# fancontrol_attiny.net
KiCad netlist of a schematic drawn in EAGLE
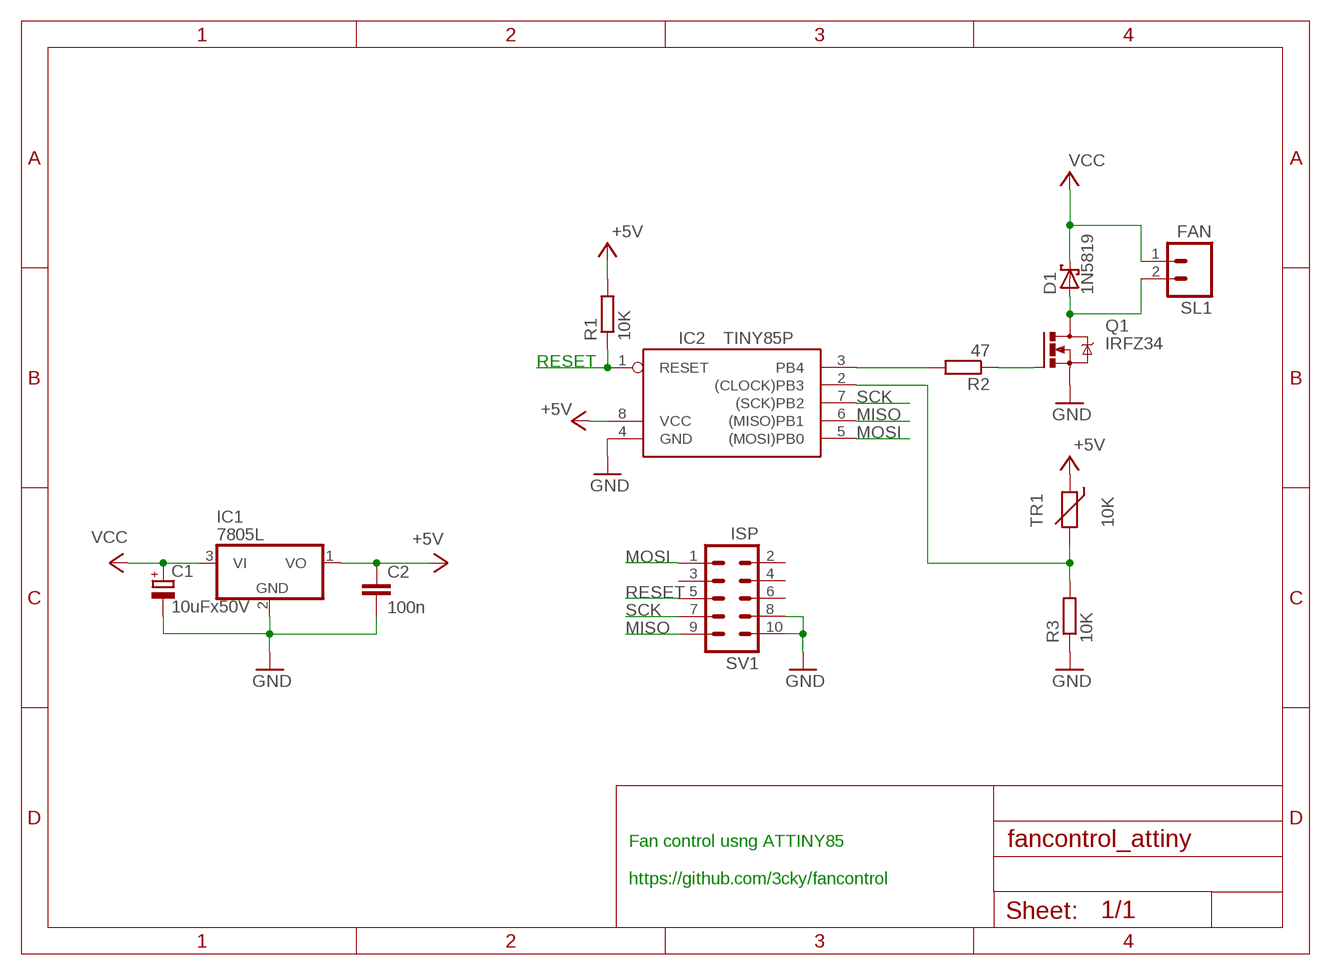
[diagram p0: schematic, sheet 1]

(export (version "E")
  (design (tool "Eeschema 10.0.6"))
  (components
    (comp (ref "C1")
      (value "10uFx50V")
      (footprint "eagle-import:E5-5")
      (libsource (lib "eagle-import") (part "CPOL-EUE5-5"))
    )
    (comp (ref "C2")
      (value "100n")
      (footprint "eagle-import:C025-024X044")
      (libsource (lib "eagle-import") (part "C-EU025-024X044"))
    )
    (comp (ref "D1")
      (value "1N5819")
      (footprint "eagle-import:DO41-7.6")
      (libsource (lib "eagle-import") (part "1N5819-B"))
    )
    (comp (ref "IC1")
      (value "7805L")
      (footprint "eagle-import:TO92")
      (libsource (lib "eagle-import") (part "78L05"))
    )
    (comp (ref "IC2")
      (value "TINY85P")
      (footprint "eagle-import:DIL08")
      (libsource (lib "eagle-import") (part "TINY22P"))
    )
    (comp (ref "Q1")
      (value "IRFZ34")
      (footprint "eagle-import:TO220BH")
      (libsource (lib "eagle-import") (part "IRFZ48Z"))
    )
    (comp (ref "R1")
      (value "10K")
      (footprint "eagle-import:M0805")
      (libsource (lib "eagle-import") (part "R-EU_M0805"))
    )
    (comp (ref "R2")
      (value "47")
      (footprint "eagle-import:M0805")
      (libsource (lib "eagle-import") (part "R-EU_M0805"))
    )
    (comp (ref "R3")
      (value "10K")
      (footprint "eagle-import:M0805")
      (libsource (lib "eagle-import") (part "R-EU_M0805"))
    )
    (comp (ref "SL1")
      (value "FAN")
      (footprint "eagle-import:02P")
      (libsource (lib "eagle-import") (part "M02"))
    )
    (comp (ref "SV1")
      (value "ISP")
      (footprint "eagle-import:MA05-2")
      (libsource (lib "eagle-import") (part "MA05-2"))
    )
    (comp (ref "TR1")
      (value "10K")
      (footprint "eagle-import:R-5")
      (libsource (lib "eagle-import") (part "THERMISTOR_R-5"))
    )
  )
  (nets
    (net (code "1") (name "+5V") (class "Default")
      (node (ref "C2") (pin "1") (pinfunction "1_1") (pintype "passive"))
      (node (ref "IC1") (pin "1") (pinfunction "VO_1") (pintype "passive"))
      (node (ref "IC2") (pin "8") (pinfunction "VCC_8") (pintype "power_in"))
      (node (ref "R1") (pin "2") (pinfunction "2_2") (pintype "passive"))
      (node (ref "TR1") (pin "1") (pinfunction "1_1") (pintype "passive"))
    )
    (net (code "2") (name "/MISO") (class "Default")
      (node (ref "IC2") (pin "6") (pinfunction "(MISO)PB1_6") (pintype "bidirectional"))
      (node (ref "SV1") (pin "9") (pinfunction "9_9") (pintype "passive"))
    )
    (net (code "3") (name "/MOSI") (class "Default")
      (node (ref "IC2") (pin "5") (pinfunction "(MOSI)PB0_5") (pintype "bidirectional"))
      (node (ref "SV1") (pin "1") (pinfunction "1_1") (pintype "passive"))
    )
    (net (code "4") (name "/RESET") (class "Default")
      (node (ref "IC2") (pin "1") (pinfunction "RESET_1") (pintype "input"))
      (node (ref "R1") (pin "1") (pinfunction "1_1") (pintype "passive"))
      (node (ref "SV1") (pin "5") (pinfunction "5_5") (pintype "passive"))
    )
    (net (code "5") (name "/SCK") (class "Default")
      (node (ref "IC2") (pin "7") (pinfunction "(SCK)PB2_7") (pintype "bidirectional"))
      (node (ref "SV1") (pin "7") (pinfunction "7_7") (pintype "passive"))
    )
    (net (code "6") (name "GND") (class "Default")
      (node (ref "C1") (pin "-") (pinfunction "-_-") (pintype "passive"))
      (node (ref "C2") (pin "2") (pinfunction "2_2") (pintype "passive"))
      (node (ref "IC1") (pin "2") (pinfunction "GND_2") (pintype "passive"))
      (node (ref "IC2") (pin "4") (pinfunction "GND_4") (pintype "power_in"))
      (node (ref "Q1") (pin "S") (pinfunction "S_S") (pintype "passive"))
      (node (ref "R3") (pin "1") (pinfunction "1_1") (pintype "passive"))
      (node (ref "SV1") (pin "10") (pinfunction "10_10") (pintype "passive"))
      (node (ref "SV1") (pin "8") (pinfunction "8_8") (pintype "passive"))
    )
    (net (code "7") (name "Net-(D1-PadA)") (class "Default")
      (node (ref "D1") (pin "A") (pinfunction "A_A") (pintype "passive"))
      (node (ref "Q1") (pin "D") (pinfunction "D_D") (pintype "passive"))
      (node (ref "SL1") (pin "2") (pinfunction "2_2") (pintype "passive"))
    )
    (net (code "8") (name "Net-(IC2-(CLOCK)PB3)") (class "Default")
      (node (ref "IC2") (pin "2") (pinfunction "(CLOCK)PB3_2") (pintype "bidirectional"))
      (node (ref "R3") (pin "2") (pinfunction "2_2") (pintype "passive"))
      (node (ref "TR1") (pin "2") (pinfunction "2_2") (pintype "passive"))
    )
    (net (code "9") (name "Net-(IC2-PB4)") (class "Default")
      (node (ref "IC2") (pin "3") (pinfunction "PB4_3") (pintype "bidirectional"))
      (node (ref "R2") (pin "2") (pinfunction "2_2") (pintype "passive"))
    )
    (net (code "10") (name "Net-(Q1-PadG)") (class "Default")
      (node (ref "Q1") (pin "G") (pinfunction "G_G") (pintype "passive"))
      (node (ref "R2") (pin "1") (pinfunction "1_1") (pintype "passive"))
    )
    (net (code "11") (name "VCC") (class "Default")
      (node (ref "C1") (pin "+") (pinfunction "+_+") (pintype "passive"))
      (node (ref "D1") (pin "C") (pinfunction "C_C") (pintype "passive"))
      (node (ref "IC1") (pin "3") (pinfunction "VI_3") (pintype "input"))
      (node (ref "SL1") (pin "1") (pinfunction "1_1") (pintype "passive"))
    )
    (net (code "12") (name "unconnected-(SV1-Pad2)") (class "Default")
      (node (ref "SV1") (pin "2") (pinfunction "2_2") (pintype "passive"))
    )
    (net (code "13") (name "unconnected-(SV1-Pad3)") (class "Default")
      (node (ref "SV1") (pin "3") (pinfunction "3_3") (pintype "passive"))
    )
    (net (code "14") (name "unconnected-(SV1-Pad4)") (class "Default")
      (node (ref "SV1") (pin "4") (pinfunction "4_4") (pintype "passive"))
    )
    (net (code "15") (name "unconnected-(SV1-Pad6)") (class "Default")
      (node (ref "SV1") (pin "6") (pinfunction "6_6") (pintype "passive"))
    )
  )
)
